# VoltageDetect.net
KiCad netlist of a schematic drawn in Altium Designer
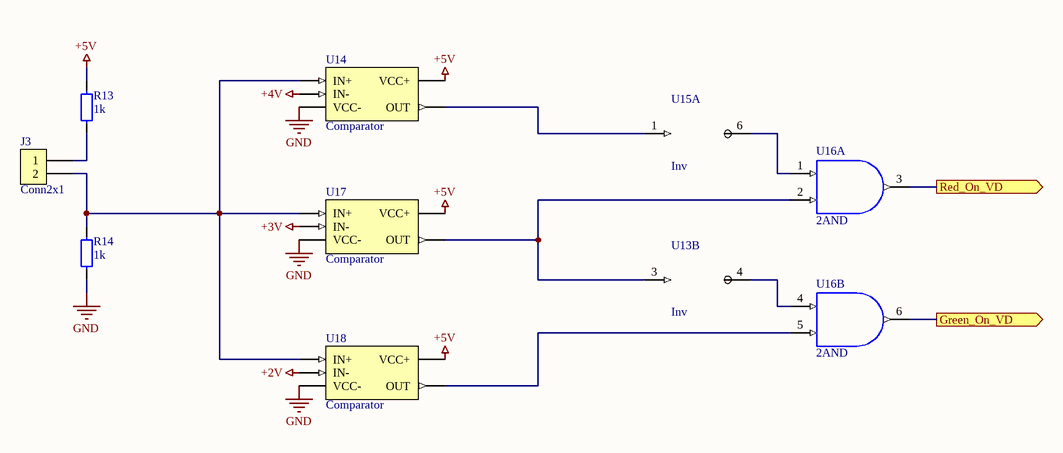
[diagram p0: VoltageDetect.SchDoc]

(export (version "E")
  (design (tool "Eeschema 10.0.6"))
  (components
    (comp (ref "J3")
      (value "Conn2x1")
      (footprint "MolexMicroFit 2x1")
      (fields (field (name "PART NUMBER") "436500200") (field (name "MANUFACTURER") "Molex"))
      (libsource (lib "BRT_Components") (part "Conn 2 [MicroFit]"))
    )
    (comp (ref "R13")
      (value "1k")
      (footprint "0603 Resistor")
      (description "0.1W 0603 1k, 1%")
      (fields (field (name "PART NUMBER") "RC0603FR-071KL") (field (name "MANUFACTURER") "Taiwan"))
      (libsource (lib "BRT_Components") (part "Res 1k (0603)"))
    )
    (comp (ref "R14")
      (value "1k")
      (footprint "0603 Resistor")
      (description "0.1W 0603 1k, 1%")
      (fields (field (name "PART NUMBER") "RC0603FR-071KL") (field (name "MANUFACTURER") "Taiwan"))
      (libsource (lib "BRT_Components") (part "Res 1k (0603)"))
    )
    (comp (ref "U13") (value "Inv") (libsource (lib "TSAL") (part "Inverter")))
    (comp (ref "U14")
      (value "Comparator")
      (footprint "SOT-23-5")
      (description "LMV7219 7-ns 2.7-V to 5-V Comparator with Rail-to-Rail Output")
      (fields
        (field (name "PART NUMBER") "LMV7219M5X/NOPB")
        (field (name "MANUFACTURER") "Texas Instruments")
      )
      (libsource (lib "BRT_Components") (part "Comparator [LMV]"))
    )
    (comp (ref "U15") (value "Inv") (libsource (lib "TSAL") (part "Inverter")))
    (comp (ref "U16")
      (value "2AND")
      (footprint "Dip14")
      (description "Quadruple 2-Input Positive-AND Gates, N0014A, TUBE")
      (libsource (lib "BRT_Components") (part "4(2AND)"))
    )
    (comp (ref "U17")
      (value "Comparator")
      (footprint "SOT-23-5")
      (description "LMV7219 7-ns 2.7-V to 5-V Comparator with Rail-to-Rail Output")
      (fields
        (field (name "PART NUMBER") "LMV7219M5X/NOPB")
        (field (name "MANUFACTURER") "Texas Instruments")
      )
      (libsource (lib "BRT_Components") (part "Comparator [LMV]"))
    )
    (comp (ref "U18")
      (value "Comparator")
      (footprint "SOT-23-5")
      (description "LMV7219 7-ns 2.7-V to 5-V Comparator with Rail-to-Rail Output")
      (fields
        (field (name "PART NUMBER") "LMV7219M5X/NOPB")
        (field (name "MANUFACTURER") "Texas Instruments")
      )
      (libsource (lib "BRT_Components") (part "Comparator [LMV]"))
    )
  )
  (nets
    (net (code "1") (name "+2V") (class "Default")
      (node (ref "U18") (pin "4") (pinfunction "IN-_4") (pintype "input"))
    )
    (net (code "2") (name "+3V") (class "Default")
      (node (ref "U17") (pin "4") (pinfunction "IN-_4") (pintype "input"))
    )
    (net (code "3") (name "+4V") (class "Default")
      (node (ref "U14") (pin "4") (pinfunction "IN-_4") (pintype "input"))
    )
    (net (code "4") (name "+5V") (class "Default")
      (node (ref "R13") (pin "2") (pinfunction "2_2") (pintype "passive"))
      (node (ref "U14") (pin "5") (pinfunction "VCC+_5") (pintype "power_in"))
      (node (ref "U17") (pin "5") (pinfunction "VCC+_5") (pintype "power_in"))
      (node (ref "U18") (pin "5") (pinfunction "VCC+_5") (pintype "power_in"))
    )
    (net (code "5") (name "/Green_On_VD") (class "Default")
      (node (ref "U16") (pin "6") (pinfunction "2Y_6") (pintype "output"))
    )
    (net (code "6") (name "/Red_On_VD") (class "Default")
      (node (ref "U16") (pin "3") (pinfunction "1Y_3") (pintype "output"))
    )
    (net (code "7") (name "GND") (class "Default")
      (node (ref "R14") (pin "1") (pinfunction "1_1") (pintype "passive"))
      (node (ref "U14") (pin "2") (pinfunction "VCC-_2") (pintype "power_in"))
      (node (ref "U17") (pin "2") (pinfunction "VCC-_2") (pintype "power_in"))
      (node (ref "U18") (pin "2") (pinfunction "VCC-_2") (pintype "power_in"))
    )
    (net (code "8") (name "Net-(J3-Pad1)") (class "Default")
      (node (ref "J3") (pin "1") (pinfunction "1_1") (pintype "passive"))
      (node (ref "R13") (pin "1") (pinfunction "1_1") (pintype "passive"))
    )
    (net (code "9") (name "Net-(U13B-A)") (class "Default")
      (node (ref "U13") (pin "3") (pinfunction "A_3") (pintype "input"))
      (node (ref "U16") (pin "2") (pinfunction "1B_2") (pintype "input"))
      (node (ref "U17") (pin "1") (pinfunction "OUT_1") (pintype "output"))
    )
    (net (code "10") (name "Net-(U13B-Y)") (class "Default")
      (node (ref "U13") (pin "4") (pinfunction "Y_4") (pintype "passive"))
      (node (ref "U16") (pin "4") (pinfunction "2A_4") (pintype "input"))
    )
    (net (code "11") (name "Net-(U14-IN+)") (class "Default")
      (node (ref "J3") (pin "2") (pinfunction "2_2") (pintype "passive"))
      (node (ref "R14") (pin "2") (pinfunction "2_2") (pintype "passive"))
      (node (ref "U14") (pin "3") (pinfunction "IN+_3") (pintype "input"))
      (node (ref "U17") (pin "3") (pinfunction "IN+_3") (pintype "input"))
      (node (ref "U18") (pin "3") (pinfunction "IN+_3") (pintype "input"))
    )
    (net (code "12") (name "Net-(U14-OUT)") (class "Default")
      (node (ref "U14") (pin "1") (pinfunction "OUT_1") (pintype "output"))
      (node (ref "U15") (pin "1") (pinfunction "A_1") (pintype "input"))
    )
    (net (code "13") (name "Net-(U15A-Y)") (class "Default")
      (node (ref "U15") (pin "6") (pinfunction "Y_6") (pintype "passive"))
      (node (ref "U16") (pin "1") (pinfunction "1A_1") (pintype "input"))
    )
    (net (code "14") (name "Net-(U16B-2B)") (class "Default")
      (node (ref "U16") (pin "5") (pinfunction "2B_5") (pintype "input"))
      (node (ref "U18") (pin "1") (pinfunction "OUT_1") (pintype "output"))
    )
  )
)
